# Adafruit_PyRuler.net
KiCad netlist of a schematic drawn in EAGLE
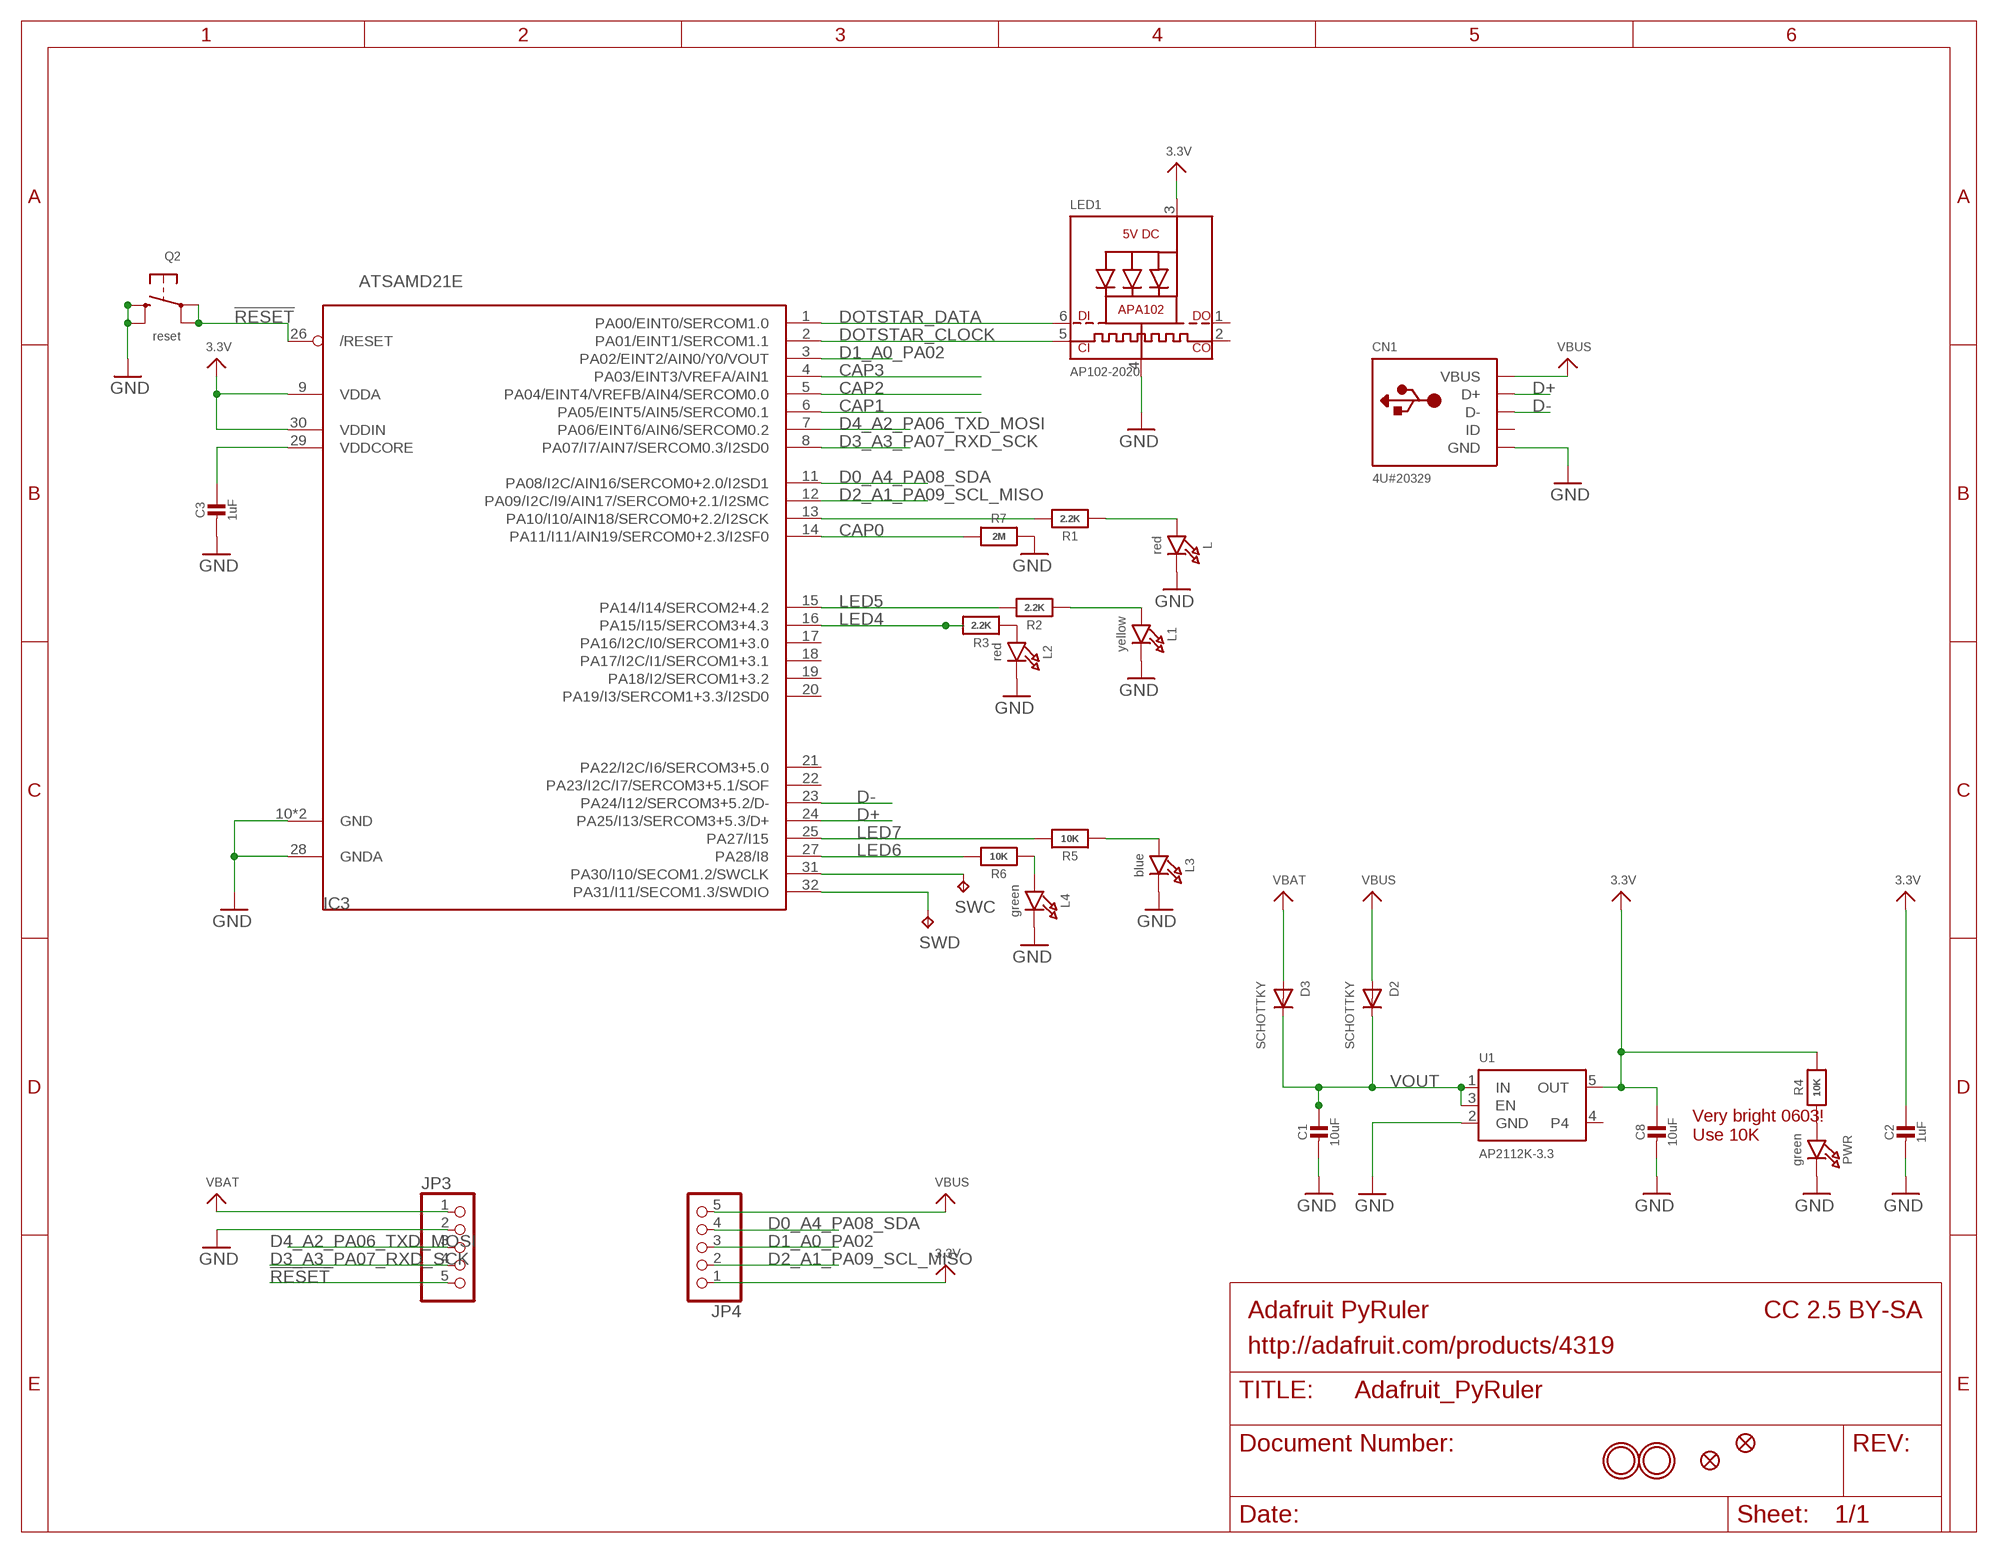
[diagram p0: schematic, sheet 1]

(export (version "E")
  (design (tool "Eeschema 10.0.6"))
  (components
    (comp (ref "C1")
      (value "10uF")
      (footprint "eagle-import:0805-NO")
      (libsource (lib "eagle-import") (part "CAP_CERAMIC0805-NOOUTLINE"))
    )
    (comp (ref "C2")
      (value "1uF")
      (footprint "eagle-import:0603-NO")
      (libsource (lib "eagle-import") (part "CAP_CERAMIC0603_NO"))
    )
    (comp (ref "C3")
      (value "1uF")
      (footprint "eagle-import:0603-NO")
      (libsource (lib "eagle-import") (part "CAP_CERAMIC0603_NO"))
    )
    (comp (ref "C8")
      (value "10uF")
      (footprint "eagle-import:0805-NO")
      (libsource (lib "eagle-import") (part "CAP_CERAMIC0805-NOOUTLINE"))
    )
    (comp (ref "CN1")
      (value "4U#20329")
      (footprint "eagle-import:4UCONN_20329_NARROW")
      (libsource (lib "eagle-import") (part "USB_MICRO_NARROW"))
    )
    (comp (ref "D2")
      (value "SCHOTTKY")
      (footprint "eagle-import:SOD-123FL")
      (libsource (lib "eagle-import") (part "DIODE_SOD-123FL"))
    )
    (comp (ref "D3")
      (value "SCHOTTKY")
      (footprint "eagle-import:SOD-123FL")
      (libsource (lib "eagle-import") (part "DIODE_SOD-123FL"))
    )
    (comp (ref "IC3")
      (value "ATSAMD21E")
      (footprint "eagle-import:QFN32_5MM")
      (libsource (lib "eagle-import") (part "ATSAMD21E"))
    )
    (comp (ref "JP3")
      (value "HEADER-1X570MIL")
      (footprint "eagle-import:1X05_ROUND_70")
      (libsource (lib "eagle-import") (part "HEADER-1X570MIL"))
    )
    (comp (ref "JP4")
      (value "HEADER-1X570MIL")
      (footprint "eagle-import:1X05_ROUND_70")
      (libsource (lib "eagle-import") (part "HEADER-1X570MIL"))
    )
    (comp (ref "L")
      (value "red")
      (footprint "eagle-import:CHIPLED_0603_NOOUTLINE")
      (libsource (lib "eagle-import") (part "LED0603_NOOUTLINE"))
    )
    (comp (ref "L1")
      (value "yellow")
      (footprint "eagle-import:CHIPLED_0603_NOOUTLINE")
      (libsource (lib "eagle-import") (part "LED0603_NOOUTLINE"))
    )
    (comp (ref "L2")
      (value "red")
      (footprint "eagle-import:CHIPLED_0603_NOOUTLINE")
      (libsource (lib "eagle-import") (part "LED0603_NOOUTLINE"))
    )
    (comp (ref "L3")
      (value "blue")
      (footprint "eagle-import:CHIPLED_0603_NOOUTLINE")
      (libsource (lib "eagle-import") (part "LED0603_NOOUTLINE"))
    )
    (comp (ref "L4")
      (value "green")
      (footprint "eagle-import:CHIPLED_0603_NOOUTLINE")
      (libsource (lib "eagle-import") (part "LED0603_NOOUTLINE"))
    )
    (comp (ref "LED1")
      (value "AP102-2020")
      (footprint "eagle-import:APA102_2020")
      (libsource (lib "eagle-import") (part "APA1022020"))
    )
    (comp (ref "PWR")
      (value "green")
      (footprint "eagle-import:CHIPLED_0603_NOOUTLINE")
      (libsource (lib "eagle-import") (part "LED0603_NOOUTLINE"))
    )
    (comp (ref "Q2")
      (value "reset")
      (footprint "eagle-import:BTN_KMR2_4.6X2.8")
      (libsource (lib "eagle-import") (part "SWITCH_TACT_SMT4.6X2.8"))
    )
    (comp (ref "R1")
      (value "2.2K")
      (footprint "eagle-import:0603-NO")
      (libsource (lib "eagle-import") (part "RESISTOR_0603_NOOUT"))
    )
    (comp (ref "R2")
      (value "2.2K")
      (footprint "eagle-import:0603-NO")
      (libsource (lib "eagle-import") (part "RESISTOR_0603_NOOUT"))
    )
    (comp (ref "R3")
      (value "2.2K")
      (footprint "eagle-import:0603-NO")
      (libsource (lib "eagle-import") (part "RESISTOR_0603_NOOUT"))
    )
    (comp (ref "R4")
      (value "10K")
      (footprint "eagle-import:0603-NO")
      (libsource (lib "eagle-import") (part "RESISTOR_0603_NOOUT"))
    )
    (comp (ref "R5")
      (value "10K")
      (footprint "eagle-import:0603-NO")
      (libsource (lib "eagle-import") (part "RESISTOR_0603_NOOUT"))
    )
    (comp (ref "R6")
      (value "10K")
      (footprint "eagle-import:0603-NO")
      (libsource (lib "eagle-import") (part "RESISTOR_0603_NOOUT"))
    )
    (comp (ref "R7")
      (value "2M")
      (footprint "eagle-import:0603-NO")
      (libsource (lib "eagle-import") (part "RESISTOR_0603_NOOUT"))
    )
    (comp (ref "SWC")
      (value "TPB1,27")
      (footprint "eagle-import:B1,27")
      (libsource (lib "eagle-import") (part "TPB1,27"))
    )
    (comp (ref "SWD")
      (value "TPB1,27")
      (footprint "eagle-import:B1,27")
      (libsource (lib "eagle-import") (part "TPB1,27"))
    )
    (comp (ref "U$1")
      (value "FIDUCIAL_1MM")
      (footprint "eagle-import:FIDUCIAL_1MM")
      (libsource (lib "eagle-import") (part "FIDUCIAL_1MM"))
    )
    (comp (ref "U$6")
      (value "FIDUCIAL_1MM")
      (footprint "eagle-import:FIDUCIAL_1MM")
      (libsource (lib "eagle-import") (part "FIDUCIAL_1MM"))
    )
    (comp (ref "U$8")
      (value "MOUNTINGHOLE2.0")
      (footprint "eagle-import:MOUNTINGHOLE_2.0_PLATED")
      (libsource (lib "eagle-import") (part "MOUNTINGHOLE2.0"))
    )
    (comp (ref "U$9")
      (value "MOUNTINGHOLE2.0")
      (footprint "eagle-import:MOUNTINGHOLE_2.0_PLATED")
      (libsource (lib "eagle-import") (part "MOUNTINGHOLE2.0"))
    )
    (comp (ref "U1")
      (value "AP2112K-3.3")
      (footprint "eagle-import:SOT23-5")
      (libsource (lib "eagle-import") (part "VREG_SOT23-5"))
    )
  )
  (nets
    (net (code "1") (name "/CAP0") (class "Default")
      (node (ref "IC3") (pin "14") (pinfunction "PA11/I11/AIN19/SERCOM0+2.3/I2SF0_14") (pintype "bidirectional"))
      (node (ref "R7") (pin "1") (pinfunction "1_1") (pintype "passive"))
    )
    (net (code "2") (name "/CAP1") (class "Default")
      (node (ref "IC3") (pin "6") (pinfunction "PA05/EINT5/AIN5/SERCOM0.1_6") (pintype "bidirectional"))
    )
    (net (code "3") (name "/CAP2") (class "Default")
      (node (ref "IC3") (pin "5") (pinfunction "PA04/EINT4/VREFB/AIN4/SERCOM0.0_5") (pintype "bidirectional"))
    )
    (net (code "4") (name "/CAP3") (class "Default")
      (node (ref "IC3") (pin "4") (pinfunction "PA03/EINT3/VREFA/AIN1_4") (pintype "bidirectional"))
    )
    (net (code "5") (name "/D+") (class "Default")
      (node (ref "CN1") (pin "D+") (pinfunction "D+_D+") (pintype "bidirectional"))
      (node (ref "IC3") (pin "24") (pinfunction "PA25/I13/SERCOM3+5.3/D+_24") (pintype "bidirectional"))
    )
    (net (code "6") (name "/D-") (class "Default")
      (node (ref "CN1") (pin "D-") (pinfunction "D-_D-") (pintype "bidirectional"))
      (node (ref "IC3") (pin "23") (pinfunction "PA24/I12/SERCOM3+5.2/D-_23") (pintype "bidirectional"))
    )
    (net (code "7") (name "/D0_A4_PA08_SDA") (class "Default")
      (node (ref "IC3") (pin "11") (pinfunction "PA08/I2C/AIN16/SERCOM0+2.0/I2SD1_11") (pintype "bidirectional"))
      (node (ref "JP4") (pin "4") (pinfunction "4_4") (pintype "passive"))
    )
    (net (code "8") (name "/D1_A0_PA02") (class "Default")
      (node (ref "IC3") (pin "3") (pinfunction "PA02/EINT2/AIN0/Y0/VOUT_3") (pintype "bidirectional"))
      (node (ref "JP4") (pin "3") (pinfunction "3_3") (pintype "passive"))
    )
    (net (code "9") (name "/D2_A1_PA09_SCL_MISO") (class "Default")
      (node (ref "IC3") (pin "12") (pinfunction "PA09/I2C/I9/AIN17/SERCOM0+2.1/I2SMC_12") (pintype "bidirectional"))
      (node (ref "JP4") (pin "2") (pinfunction "2_2") (pintype "passive"))
    )
    (net (code "10") (name "/D3_A3_PA07_RXD_SCK") (class "Default")
      (node (ref "IC3") (pin "8") (pinfunction "PA07/I7/AIN7/SERCOM0.3/I2SD0_8") (pintype "bidirectional"))
      (node (ref "JP3") (pin "4") (pinfunction "4_4") (pintype "passive"))
    )
    (net (code "11") (name "/D4_A2_PA06_TXD_MOSI") (class "Default")
      (node (ref "IC3") (pin "7") (pinfunction "PA06/EINT6/AIN6/SERCOM0.2_7") (pintype "bidirectional"))
      (node (ref "JP3") (pin "3") (pinfunction "3_3") (pintype "passive"))
    )
    (net (code "12") (name "/DOTSTAR_CLOCK") (class "Default")
      (node (ref "IC3") (pin "2") (pinfunction "PA01/EINT1/SERCOM1.1_2") (pintype "bidirectional"))
      (node (ref "LED1") (pin "5") (pinfunction "CKI_5") (pintype "input"))
    )
    (net (code "13") (name "/DOTSTAR_DATA") (class "Default")
      (node (ref "IC3") (pin "1") (pinfunction "PA00/EINT0/SERCOM1.0_1") (pintype "bidirectional"))
      (node (ref "LED1") (pin "6") (pinfunction "DI_6") (pintype "input"))
    )
    (net (code "14") (name "/LED4") (class "Default")
      (node (ref "IC3") (pin "16") (pinfunction "PA15/I15/SERCOM3+4.3_16") (pintype "bidirectional"))
      (node (ref "R3") (pin "2") (pinfunction "2_2") (pintype "passive"))
    )
    (net (code "15") (name "/LED5") (class "Default")
      (node (ref "IC3") (pin "15") (pinfunction "PA14/I14/SERCOM2+4.2_15") (pintype "bidirectional"))
      (node (ref "R2") (pin "2") (pinfunction "2_2") (pintype "passive"))
    )
    (net (code "16") (name "/LED6") (class "Default")
      (node (ref "IC3") (pin "27") (pinfunction "PA28/I8_27") (pintype "bidirectional"))
      (node (ref "R6") (pin "2") (pinfunction "2_2") (pintype "passive"))
    )
    (net (code "17") (name "/LED7") (class "Default")
      (node (ref "IC3") (pin "25") (pinfunction "PA27/I15_25") (pintype "bidirectional"))
      (node (ref "R5") (pin "2") (pinfunction "2_2") (pintype "passive"))
    )
    (net (code "18") (name "/VOUT") (class "Default")
      (node (ref "C1") (pin "1") (pinfunction "1_1") (pintype "passive"))
      (node (ref "D2") (pin "C") (pinfunction "C_C") (pintype "passive"))
      (node (ref "D3") (pin "C") (pinfunction "C_C") (pintype "passive"))
      (node (ref "U1") (pin "1") (pinfunction "IN_1") (pintype "power_in"))
      (node (ref "U1") (pin "3") (pinfunction "EN_3") (pintype "input"))
    )
    (net (code "19") (name "/~{RESET}") (class "Default")
      (node (ref "IC3") (pin "26") (pinfunction "/RESET_26") (pintype "bidirectional"))
      (node (ref "JP3") (pin "5") (pinfunction "5_5") (pintype "passive"))
      (node (ref "Q2") (pin "A") (pinfunction "P_A") (pintype "passive"))
      (node (ref "Q2") (pin "A'") (pinfunction "P1_A'") (pintype "passive"))
    )
    (net (code "20") (name "3.3V") (class "Default")
      (node (ref "C2") (pin "1") (pinfunction "1_1") (pintype "passive"))
      (node (ref "C8") (pin "1") (pinfunction "1_1") (pintype "passive"))
      (node (ref "IC3") (pin "30") (pinfunction "VDDIN_30") (pintype "power_in"))
      (node (ref "IC3") (pin "9") (pinfunction "VDDA_9") (pintype "power_in"))
      (node (ref "JP4") (pin "1") (pinfunction "1_1") (pintype "passive"))
      (node (ref "LED1") (pin "3") (pinfunction "VDD_3") (pintype "power_in"))
      (node (ref "R4") (pin "2") (pinfunction "2_2") (pintype "passive"))
      (node (ref "U1") (pin "5") (pinfunction "OUT_5") (pintype "power_in"))
    )
    (net (code "21") (name "GND") (class "Default")
      (node (ref "C1") (pin "2") (pinfunction "2_2") (pintype "passive"))
      (node (ref "C2") (pin "2") (pinfunction "2_2") (pintype "passive"))
      (node (ref "C3") (pin "2") (pinfunction "2_2") (pintype "passive"))
      (node (ref "C8") (pin "2") (pinfunction "2_2") (pintype "passive"))
      (node (ref "CN1") (pin "BASE@1") (pinfunction "GND_BASE@1") (pintype "power_in"))
      (node (ref "CN1") (pin "BASE@2") (pinfunction "GND_BASE@2") (pintype "power_in"))
      (node (ref "CN1") (pin "GND") (pinfunction "GND_GND") (pintype "power_in"))
      (node (ref "CN1") (pin "SPRT@1") (pinfunction "GND_SPRT@1") (pintype "power_in"))
      (node (ref "CN1") (pin "SPRT@2") (pinfunction "GND_SPRT@2") (pintype "power_in"))
      (node (ref "CN1") (pin "SPRT@3") (pinfunction "GND_SPRT@3") (pintype "power_in"))
      (node (ref "CN1") (pin "SPRT@4") (pinfunction "GND_SPRT@4") (pintype "power_in"))
      (node (ref "IC3") (pin "10") (pinfunction "GND_10") (pintype "power_in"))
      (node (ref "IC3") (pin "28") (pinfunction "GNDA_28") (pintype "power_in"))
      (node (ref "IC3") (pin "33") (pinfunction "GND_33") (pintype "power_in"))
      (node (ref "JP3") (pin "2") (pinfunction "2_2") (pintype "passive"))
      (node (ref "L") (pin "C") (pinfunction "C_C") (pintype "passive"))
      (node (ref "L1") (pin "C") (pinfunction "C_C") (pintype "passive"))
      (node (ref "L2") (pin "C") (pinfunction "C_C") (pintype "passive"))
      (node (ref "L3") (pin "C") (pinfunction "C_C") (pintype "passive"))
      (node (ref "L4") (pin "C") (pinfunction "C_C") (pintype "passive"))
      (node (ref "LED1") (pin "4") (pinfunction "GND_4") (pintype "power_in"))
      (node (ref "PWR") (pin "C") (pinfunction "C_C") (pintype "passive"))
      (node (ref "Q2") (pin "B") (pinfunction "S_B") (pintype "passive"))
      (node (ref "Q2") (pin "B'") (pinfunction "S1_B'") (pintype "passive"))
      (node (ref "R7") (pin "2") (pinfunction "2_2") (pintype "passive"))
      (node (ref "U1") (pin "2") (pinfunction "GND_2") (pintype "power_in"))
    )
    (net (code "22") (name "Net-(IC3-PA10{slash}I10{slash}AIN18{slash}SERCOM0+2.2{slash}I2SCK)") (class "Default")
      (node (ref "IC3") (pin "13") (pinfunction "PA10/I10/AIN18/SERCOM0+2.2/I2SCK_13") (pintype "bidirectional"))
      (node (ref "R1") (pin "2") (pinfunction "2_2") (pintype "passive"))
    )
    (net (code "23") (name "Net-(IC3-PA30{slash}I10{slash}SECOM1.2{slash}SWCLK)") (class "Default")
      (node (ref "IC3") (pin "31") (pinfunction "PA30/I10/SECOM1.2/SWCLK_31") (pintype "bidirectional"))
      (node (ref "SWC") (pin "TP") (pinfunction "TP_TP") (pintype "input"))
    )
    (net (code "24") (name "Net-(IC3-PA31{slash}I11{slash}SECOM1.3{slash}SWDIO)") (class "Default")
      (node (ref "IC3") (pin "32") (pinfunction "PA31/I11/SECOM1.3/SWDIO_32") (pintype "bidirectional"))
      (node (ref "SWD") (pin "TP") (pinfunction "TP_TP") (pintype "input"))
    )
    (net (code "25") (name "Net-(IC3-VDDCORE)") (class "Default")
      (node (ref "C3") (pin "1") (pinfunction "1_1") (pintype "passive"))
      (node (ref "IC3") (pin "29") (pinfunction "VDDCORE_29") (pintype "power_in"))
    )
    (net (code "26") (name "Net-(L-PadA)") (class "Default")
      (node (ref "L") (pin "A") (pinfunction "A_A") (pintype "passive"))
      (node (ref "R1") (pin "1") (pinfunction "1_1") (pintype "passive"))
    )
    (net (code "27") (name "Net-(L1-PadA)") (class "Default")
      (node (ref "L1") (pin "A") (pinfunction "A_A") (pintype "passive"))
      (node (ref "R2") (pin "1") (pinfunction "1_1") (pintype "passive"))
    )
    (net (code "28") (name "Net-(L2-PadA)") (class "Default")
      (node (ref "L2") (pin "A") (pinfunction "A_A") (pintype "passive"))
      (node (ref "R3") (pin "1") (pinfunction "1_1") (pintype "passive"))
    )
    (net (code "29") (name "Net-(L3-PadA)") (class "Default")
      (node (ref "L3") (pin "A") (pinfunction "A_A") (pintype "passive"))
      (node (ref "R5") (pin "1") (pinfunction "1_1") (pintype "passive"))
    )
    (net (code "30") (name "Net-(L4-PadA)") (class "Default")
      (node (ref "L4") (pin "A") (pinfunction "A_A") (pintype "passive"))
      (node (ref "R6") (pin "1") (pinfunction "1_1") (pintype "passive"))
    )
    (net (code "31") (name "Net-(PWR-PadA)") (class "Default")
      (node (ref "PWR") (pin "A") (pinfunction "A_A") (pintype "passive"))
      (node (ref "R4") (pin "1") (pinfunction "1_1") (pintype "passive"))
    )
    (net (code "32") (name "VBAT") (class "Default")
      (node (ref "D3") (pin "A") (pinfunction "A_A") (pintype "passive"))
      (node (ref "JP3") (pin "1") (pinfunction "1_1") (pintype "passive"))
    )
    (net (code "33") (name "VBUS") (class "Default")
      (node (ref "CN1") (pin "VBUS") (pinfunction "VBUS_VBUS") (pintype "power_in"))
      (node (ref "D2") (pin "A") (pinfunction "A_A") (pintype "passive"))
      (node (ref "JP4") (pin "5") (pinfunction "5_5") (pintype "passive"))
    )
    (net (code "34") (name "unconnected-(CN1-PadID)") (class "Default")
      (node (ref "CN1") (pin "ID") (pinfunction "ID_ID") (pintype "bidirectional"))
    )
    (net (code "35") (name "unconnected-(IC3-PA16{slash}I2C{slash}I0{slash}SERCOM1+3.0-Pad17)") (class "Default")
      (node (ref "IC3") (pin "17") (pinfunction "PA16/I2C/I0/SERCOM1+3.0_17") (pintype "bidirectional"))
    )
    (net (code "36") (name "unconnected-(IC3-PA17{slash}I2C{slash}I1{slash}SERCOM1+3.1-Pad18)") (class "Default")
      (node (ref "IC3") (pin "18") (pinfunction "PA17/I2C/I1/SERCOM1+3.1_18") (pintype "bidirectional"))
    )
    (net (code "37") (name "unconnected-(IC3-PA18{slash}I2{slash}SERCOM1+3.2-Pad19)") (class "Default")
      (node (ref "IC3") (pin "19") (pinfunction "PA18/I2/SERCOM1+3.2_19") (pintype "bidirectional"))
    )
    (net (code "38") (name "unconnected-(IC3-PA19{slash}I3{slash}SERCOM1+3.3{slash}I2SD0-Pad20)") (class "Default")
      (node (ref "IC3") (pin "20") (pinfunction "PA19/I3/SERCOM1+3.3/I2SD0_20") (pintype "bidirectional"))
    )
    (net (code "39") (name "unconnected-(IC3-PA22{slash}I2C{slash}I6{slash}SERCOM3+5.0-Pad21)") (class "Default")
      (node (ref "IC3") (pin "21") (pinfunction "PA22/I2C/I6/SERCOM3+5.0_21") (pintype "bidirectional"))
    )
    (net (code "40") (name "unconnected-(IC3-PA23{slash}I2C{slash}I7{slash}SERCOM3+5.1{slash}SOF-Pad22)") (class "Default")
      (node (ref "IC3") (pin "22") (pinfunction "PA23/I2C/I7/SERCOM3+5.1/SOF_22") (pintype "bidirectional"))
    )
    (net (code "41") (name "unconnected-(LED1-CKO-Pad2)") (class "Default")
      (node (ref "LED1") (pin "2") (pinfunction "CKO_2") (pintype "output"))
    )
    (net (code "42") (name "unconnected-(LED1-DO-Pad1)") (class "Default")
      (node (ref "LED1") (pin "1") (pinfunction "DO_1") (pintype "output"))
    )
    (net (code "43") (name "unconnected-(U1-P4-Pad4)") (class "Default")
      (node (ref "U1") (pin "4") (pinfunction "P4_4") (pintype "bidirectional"))
    )
  )
)
